# D1_-_TH_LCD_Dupont_RJ45.net
KiCad netlist of a schematic drawn in EAGLE
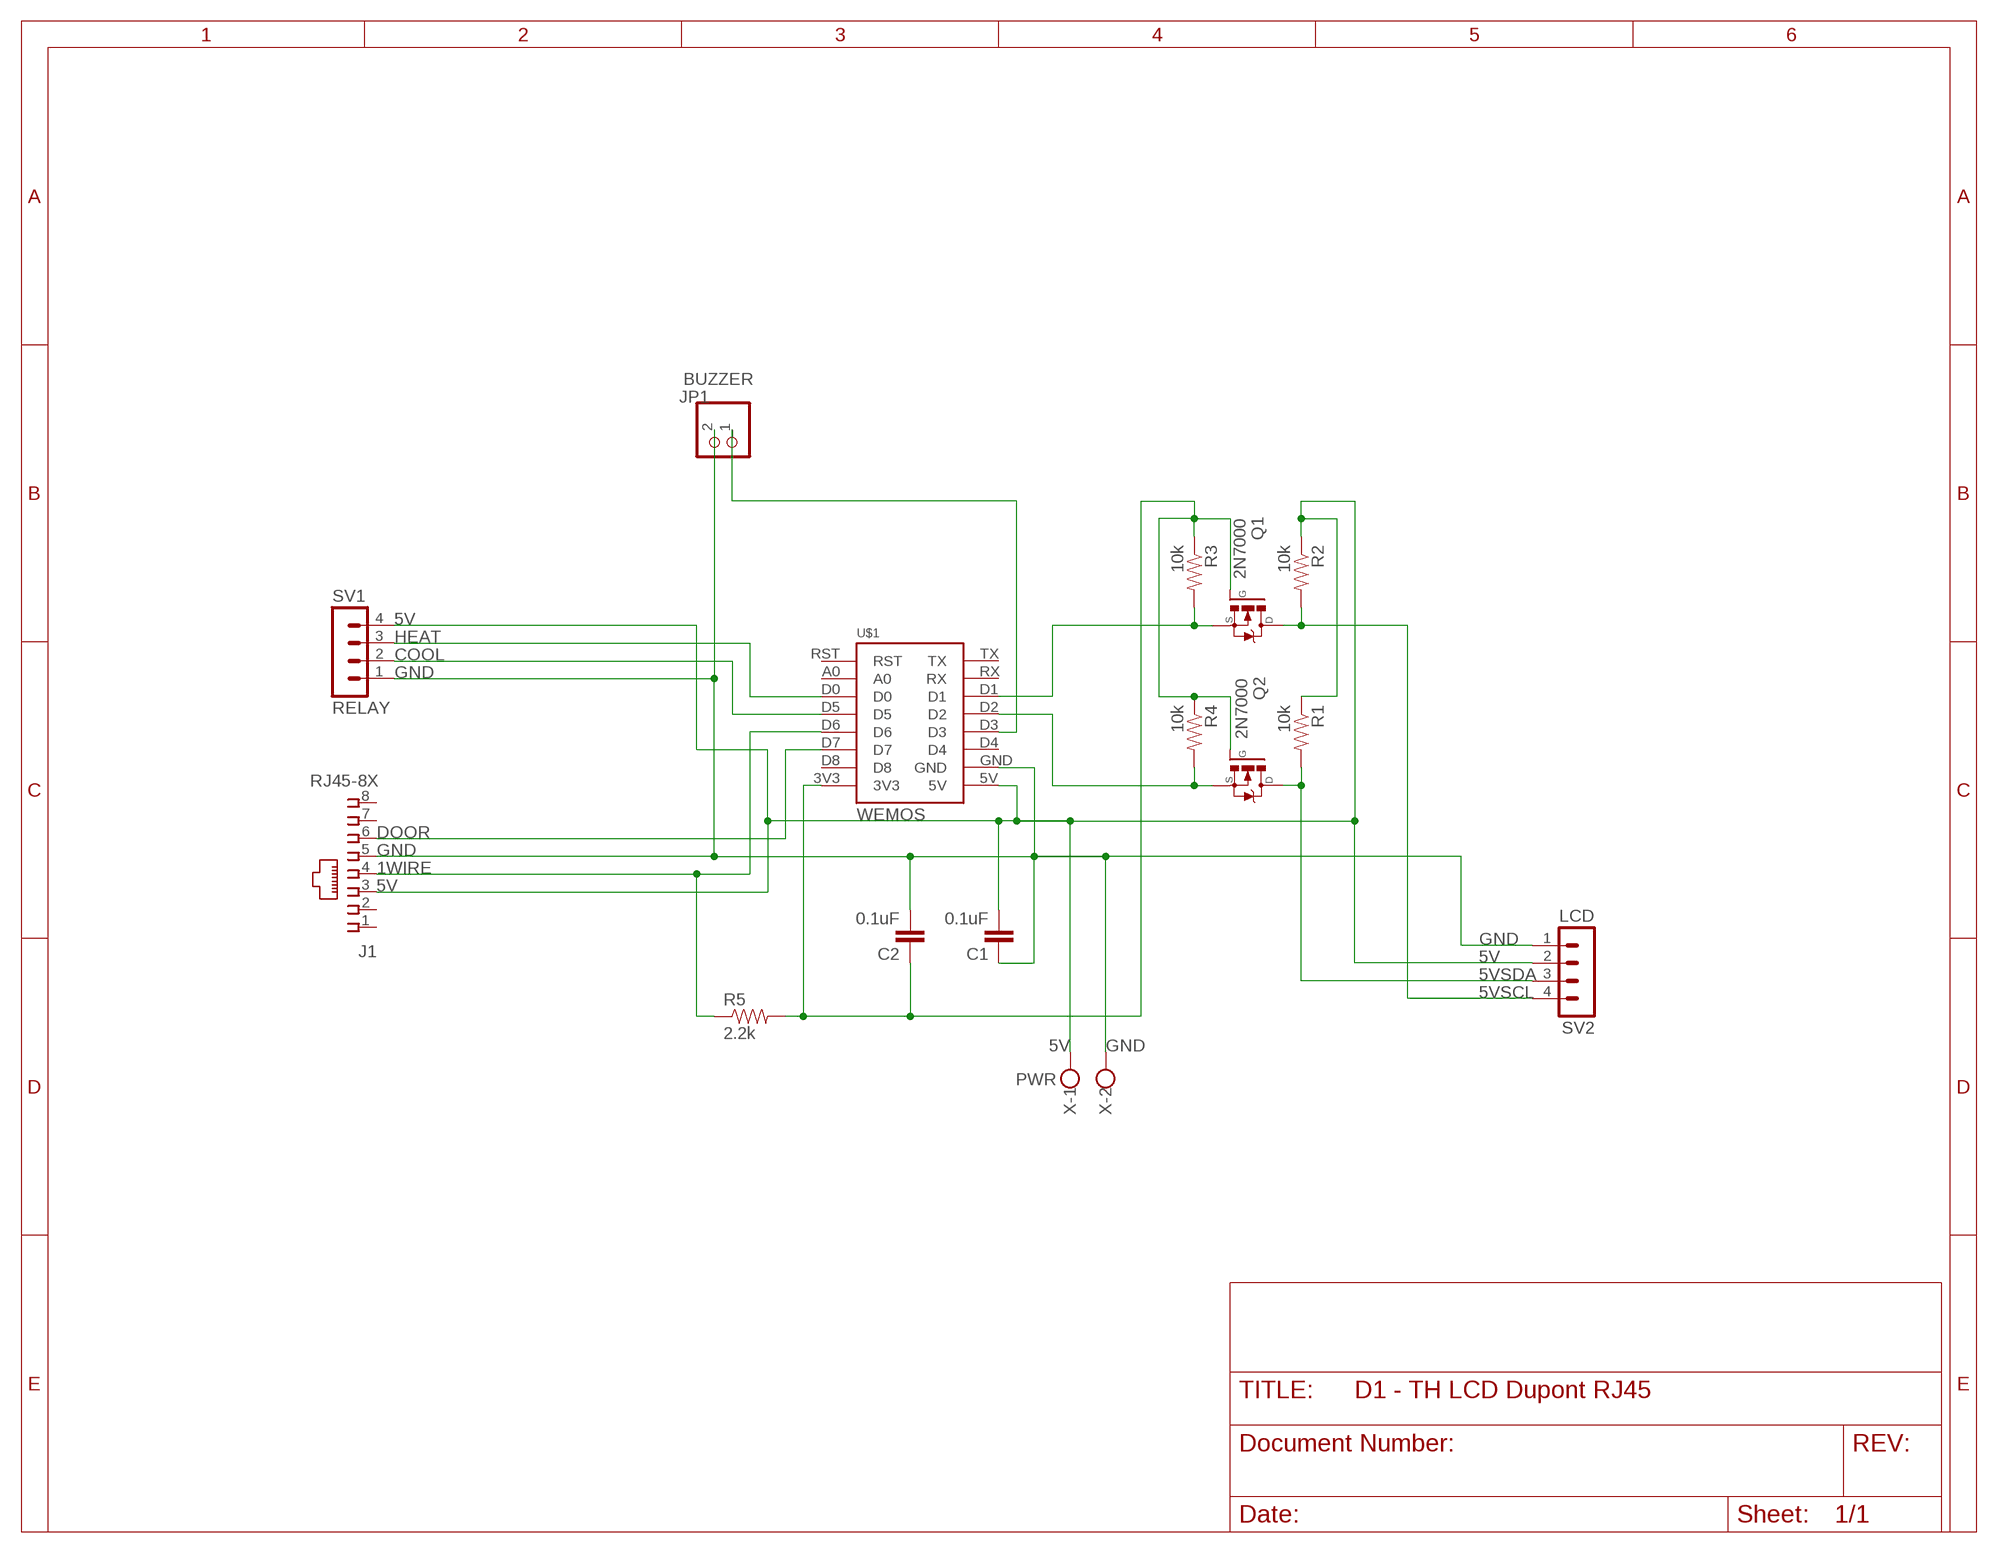
[diagram p0: schematic, sheet 1]

(export (version "E")
  (design (tool "Eeschema 10.0.6"))
  (components
    (comp (ref "BUZZER")
      (value "JP1")
      (footprint "eagle-import:1X02")
      (libsource (lib "eagle-import") (part "PINHD-1X2"))
    )
    (comp (ref "C1")
      (value "0.1uF")
      (footprint "eagle-import:C025-024X044")
      (libsource (lib "eagle-import") (part "C-EU025-024X044"))
    )
    (comp (ref "C2")
      (value "0.1uF")
      (footprint "eagle-import:C025-024X044")
      (libsource (lib "eagle-import") (part "C-EU025-024X044"))
    )
    (comp (ref "J1")
      (value "RJ45-8X")
      (footprint "eagle-import:RJ45-NO-SHIELD-NOLINE")
      (libsource (lib "eagle-import") (part "RJ45-8X"))
    )
    (comp (ref "Q1")
      (value "2N7000")
      (footprint "eagle-import:TO-92")
      (libsource (lib "eagle-import") (part "2N7000"))
    )
    (comp (ref "Q2")
      (value "2N7000")
      (footprint "eagle-import:TO-92")
      (libsource (lib "eagle-import") (part "2N7000"))
    )
    (comp (ref "R1")
      (value "10k")
      (footprint "eagle-import:AXIAL-0.3")
      (libsource (lib "eagle-import") (part "10KOHM-HORIZ-1/4W-1%"))
    )
    (comp (ref "R2")
      (value "10k")
      (footprint "eagle-import:AXIAL-0.3")
      (libsource (lib "eagle-import") (part "10KOHM-HORIZ-1/4W-1%"))
    )
    (comp (ref "R3")
      (value "10k")
      (footprint "eagle-import:AXIAL-0.3")
      (libsource (lib "eagle-import") (part "10KOHM-HORIZ-1/4W-1%"))
    )
    (comp (ref "R4")
      (value "10k")
      (footprint "eagle-import:AXIAL-0.3")
      (libsource (lib "eagle-import") (part "10KOHM-HORIZ-1/4W-1%"))
    )
    (comp (ref "R5")
      (value "2.2k")
      (footprint "eagle-import:AXIAL-0.3")
      (libsource (lib "eagle-import") (part "10KOHM-HORIZ-1/4W-1%"))
    )
    (comp (ref "SV1")
      (value "RELAY")
      (footprint "eagle-import:MA04-1")
      (libsource (lib "eagle-import") (part "MA04-1"))
    )
    (comp (ref "SV2")
      (value "LCD")
      (footprint "eagle-import:MA04-1")
      (libsource (lib "eagle-import") (part "MA04-1"))
    )
    (comp (ref "U$1")
      (value "WEMOS")
      (footprint "eagle-import:WEMOS")
      (libsource (lib "eagle-import") (part "WEMOS"))
    )
    (comp (ref "X")
      (value "PWR")
      (footprint "eagle-import:W237-102")
      (fields (field (name "MPN") "237-102"))
      (libsource (lib "eagle-import") (part "W237-102"))
    )
  )
  (nets
    (net (code "1") (name "/1WIRE") (class "Default")
      (node (ref "J1") (pin "4") (pinfunction "4_4") (pintype "passive"))
      (node (ref "R5") (pin "P$1") (pinfunction "1_P$1") (pintype "passive"))
      (node (ref "U$1") (pin "D6") (pinfunction "D6_D6") (pintype "bidirectional"))
    )
    (net (code "2") (name "/5V") (class "Default")
      (node (ref "C1") (pin "2") (pinfunction "2_2") (pintype "passive"))
      (node (ref "J1") (pin "3") (pinfunction "3_3") (pintype "passive"))
      (node (ref "R1") (pin "P$1") (pinfunction "1_P$1") (pintype "passive"))
      (node (ref "R2") (pin "P$1") (pinfunction "1_P$1") (pintype "passive"))
      (node (ref "SV1") (pin "4") (pinfunction "4_4") (pintype "passive"))
      (node (ref "SV2") (pin "2") (pinfunction "2_2") (pintype "passive"))
      (node (ref "U$1") (pin "5V") (pinfunction "5V_5V") (pintype "bidirectional"))
      (node (ref "X") (pin "1") (pinfunction "KL_1") (pintype "passive"))
    )
    (net (code "3") (name "/5VSCL") (class "Default")
      (node (ref "Q1") (pin "3") (pinfunction "D_3") (pintype "passive"))
      (node (ref "R2") (pin "P$2") (pinfunction "2_P$2") (pintype "passive"))
      (node (ref "SV2") (pin "4") (pinfunction "4_4") (pintype "passive"))
    )
    (net (code "4") (name "/5VSDA") (class "Default")
      (node (ref "Q2") (pin "3") (pinfunction "D_3") (pintype "passive"))
      (node (ref "R1") (pin "P$2") (pinfunction "2_P$2") (pintype "passive"))
      (node (ref "SV2") (pin "3") (pinfunction "3_3") (pintype "passive"))
    )
    (net (code "5") (name "/COOL") (class "Default")
      (node (ref "SV1") (pin "2") (pinfunction "2_2") (pintype "passive"))
      (node (ref "U$1") (pin "D5") (pinfunction "D5_D5") (pintype "bidirectional"))
    )
    (net (code "6") (name "/DOOR") (class "Default")
      (node (ref "J1") (pin "6") (pinfunction "6_6") (pintype "passive"))
      (node (ref "U$1") (pin "D7") (pinfunction "D7_D7") (pintype "bidirectional"))
    )
    (net (code "7") (name "/GND") (class "Default")
      (node (ref "BUZZER") (pin "2") (pinfunction "2_2") (pintype "passive"))
      (node (ref "C1") (pin "1") (pinfunction "1_1") (pintype "passive"))
      (node (ref "C2") (pin "2") (pinfunction "2_2") (pintype "passive"))
      (node (ref "J1") (pin "5") (pinfunction "5_5") (pintype "passive"))
      (node (ref "SV1") (pin "1") (pinfunction "1_1") (pintype "passive"))
      (node (ref "SV2") (pin "1") (pinfunction "1_1") (pintype "passive"))
      (node (ref "U$1") (pin "GND") (pinfunction "GND_GND") (pintype "bidirectional"))
      (node (ref "X") (pin "2") (pinfunction "KL_2") (pintype "passive"))
    )
    (net (code "8") (name "/HEAT") (class "Default")
      (node (ref "SV1") (pin "3") (pinfunction "3_3") (pintype "passive"))
      (node (ref "U$1") (pin "D0") (pinfunction "D0_D0") (pintype "bidirectional"))
    )
    (net (code "9") (name "Net-(BUZZER-Pad1)") (class "Default")
      (node (ref "BUZZER") (pin "1") (pinfunction "1_1") (pintype "passive"))
      (node (ref "U$1") (pin "D3") (pinfunction "D3_D3") (pintype "bidirectional"))
    )
    (net (code "10") (name "Net-(Q1-G)") (class "Default")
      (node (ref "C2") (pin "1") (pinfunction "1_1") (pintype "passive"))
      (node (ref "Q1") (pin "2") (pinfunction "G_2") (pintype "passive"))
      (node (ref "Q2") (pin "2") (pinfunction "G_2") (pintype "passive"))
      (node (ref "R3") (pin "P$1") (pinfunction "1_P$1") (pintype "passive"))
      (node (ref "R4") (pin "P$1") (pinfunction "1_P$1") (pintype "passive"))
      (node (ref "R5") (pin "P$2") (pinfunction "2_P$2") (pintype "passive"))
      (node (ref "U$1") (pin "3V3") (pinfunction "3V3_3V3") (pintype "bidirectional"))
    )
    (net (code "11") (name "Net-(Q1-S)") (class "Default")
      (node (ref "Q1") (pin "1") (pinfunction "S_1") (pintype "passive"))
      (node (ref "R3") (pin "P$2") (pinfunction "2_P$2") (pintype "passive"))
      (node (ref "U$1") (pin "D1") (pinfunction "D1_D1") (pintype "bidirectional"))
    )
    (net (code "12") (name "Net-(Q2-S)") (class "Default")
      (node (ref "Q2") (pin "1") (pinfunction "S_1") (pintype "passive"))
      (node (ref "R4") (pin "P$2") (pinfunction "2_P$2") (pintype "passive"))
      (node (ref "U$1") (pin "D2") (pinfunction "D2_D2") (pintype "bidirectional"))
    )
    (net (code "13") (name "unconnected-(J1-Pad1)") (class "Default")
      (node (ref "J1") (pin "1") (pinfunction "1_1") (pintype "passive"))
    )
    (net (code "14") (name "unconnected-(J1-Pad2)") (class "Default")
      (node (ref "J1") (pin "2") (pinfunction "2_2") (pintype "passive"))
    )
    (net (code "15") (name "unconnected-(J1-Pad7)") (class "Default")
      (node (ref "J1") (pin "7") (pinfunction "7_7") (pintype "passive"))
    )
    (net (code "16") (name "unconnected-(J1-Pad8)") (class "Default")
      (node (ref "J1") (pin "8") (pinfunction "8_8") (pintype "passive"))
    )
    (net (code "17") (name "unconnected-(U$1-PadA0)") (class "Default")
      (node (ref "U$1") (pin "A0") (pinfunction "A0_A0") (pintype "bidirectional"))
    )
    (net (code "18") (name "unconnected-(U$1-PadD4)") (class "Default")
      (node (ref "U$1") (pin "D4") (pinfunction "D4_D4") (pintype "bidirectional"))
    )
    (net (code "19") (name "unconnected-(U$1-PadD8)") (class "Default")
      (node (ref "U$1") (pin "D8") (pinfunction "D8_D8") (pintype "bidirectional"))
    )
    (net (code "20") (name "unconnected-(U$1-PadRST)") (class "Default")
      (node (ref "U$1") (pin "RST") (pinfunction "RST_RST") (pintype "bidirectional"))
    )
    (net (code "21") (name "unconnected-(U$1-PadRX)") (class "Default")
      (node (ref "U$1") (pin "RX") (pinfunction "RX_RX") (pintype "bidirectional"))
    )
    (net (code "22") (name "unconnected-(U$1-PadTX)") (class "Default")
      (node (ref "U$1") (pin "TX") (pinfunction "TX_TX") (pintype "bidirectional"))
    )
  )
)
